# H-00488_-_Connectors_Upstream.net
KiCad netlist of a schematic drawn in Altium Designer
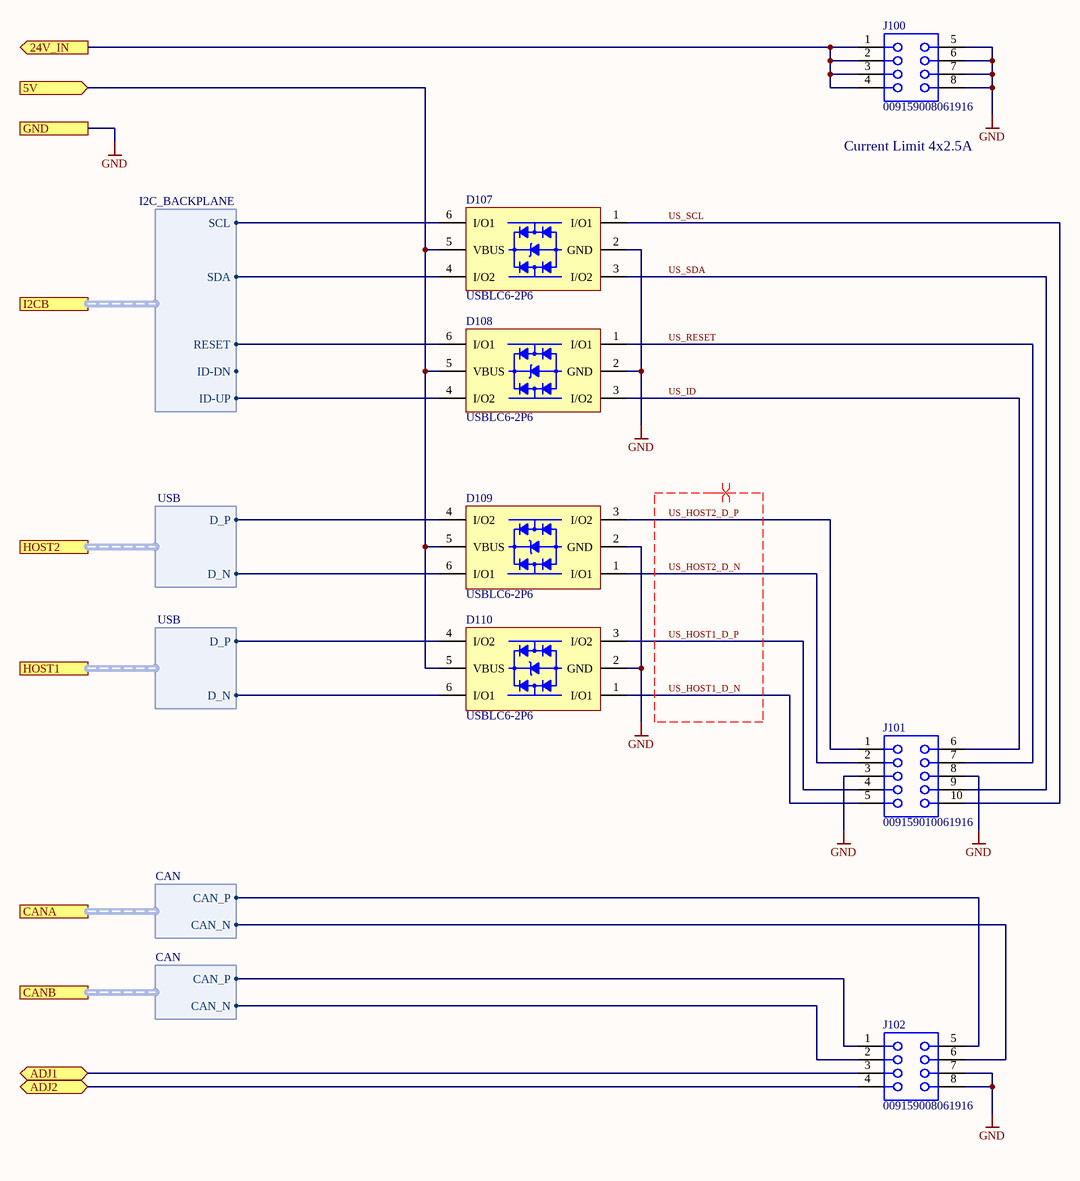
[diagram p0: H-00488 - Connectors Upstream.SchDoc]

(export (version "E")
  (design (tool "Eeschema 10.0.6"))
  (components
    (comp (ref "D107")
      (value "USBLC6-2P6")
      (footprint "DIOSOFL6P50_160X160X95L29X26")
      (description "TVS DIODE 5.25VWM 17VC SOT666")
      (libsource (lib "") (part "ST_USBLC6-2_1"))
    )
    (comp (ref "D108")
      (value "USBLC6-2P6")
      (footprint "DIOSOFL6P50_160X160X95L29X26")
      (description "TVS DIODE 5.25VWM 17VC SOT666")
      (libsource (lib "") (part "ST_USBLC6-2_1"))
    )
    (comp (ref "D109")
      (value "USBLC6-2P6")
      (footprint "DIOSOFL6P50_160X160X95L29X26")
      (description "TVS DIODE 5.25VWM 17VC SOT666")
      (libsource (lib "Hiber") (part "ST_USBLC6-2"))
    )
    (comp (ref "D110")
      (value "USBLC6-2P6")
      (footprint "DIOSOFL6P50_160X160X95L29X26")
      (description "TVS DIODE 5.25VWM 17VC SOT666")
      (libsource (lib "Hiber") (part "ST_USBLC6-2"))
    )
    (comp (ref "J100")
      (value "009159008061916")
      (footprint "AVX_00-9159-008")
      (description "CONN SSL BRIDGE 8POS 2MM")
      (libsource (lib "Hiber") (part "HEADER-FEMALE-02X04-N"))
    )
    (comp (ref "J101")
      (value "009159010061916")
      (footprint "AVX_00-9159-010")
      (description "AVX INTERCONNECT - 009159010061916 - CARD EDGE CONN, DUAL SIDE, 10POS, SMD")
      (libsource (lib "Hiber") (part "HEADER-FEMALE-02X05-N"))
    )
    (comp (ref "J102")
      (value "009159008061916")
      (footprint "AVX_00-9159-008")
      (description "CONN SSL BRIDGE 8POS 2MM")
      (libsource (lib "Hiber") (part "HEADER-FEMALE-02X04-N"))
    )
  )
  (nets
    (net (code "4") (name "/5V") (class "Default")
      (node (ref "D107") (pin "5") (pinfunction "VBUS_5") (pintype "passive"))
      (node (ref "D108") (pin "5") (pinfunction "VBUS_5") (pintype "passive"))
      (node (ref "D109") (pin "5") (pinfunction "VBUS_5") (pintype "passive"))
      (node (ref "D110") (pin "5") (pinfunction "VBUS_5") (pintype "passive"))
    )
    (net (code "5") (name "/24V_IN") (class "Default")
      (node (ref "J100") (pin "1") (pinfunction "1_1") (pintype "passive"))
      (node (ref "J100") (pin "2") (pinfunction "2_2") (pintype "passive"))
      (node (ref "J100") (pin "3") (pinfunction "3_3") (pintype "passive"))
      (node (ref "J100") (pin "4") (pinfunction "4_4") (pintype "passive"))
    )
    (net (code "6") (name "/ADJ1") (class "Default")
      (node (ref "J102") (pin "3") (pinfunction "3_3") (pintype "passive"))
    )
    (net (code "7") (name "/ADJ2") (class "Default")
      (node (ref "J102") (pin "4") (pinfunction "4_4") (pintype "passive"))
    )
    (net (code "8") (name "/ID-UP") (class "Default")
      (node (ref "D108") (pin "4") (pinfunction "I/O2_4") (pintype "passive"))
    )
    (net (code "9") (name "/RESET") (class "Default")
      (node (ref "D108") (pin "6") (pinfunction "I/O1_6") (pintype "passive"))
    )
    (net (code "10") (name "/SCL") (class "Default")
      (node (ref "D107") (pin "6") (pinfunction "I/O1_6") (pintype "passive"))
    )
    (net (code "11") (name "/SDA") (class "Default")
      (node (ref "D107") (pin "4") (pinfunction "I/O2_4") (pintype "passive"))
    )
    (net (code "12") (name "/US_HOST1_D_N") (class "Default")
      (node (ref "D110") (pin "1") (pinfunction "I/O1_1") (pintype "passive"))
      (node (ref "J101") (pin "5") (pinfunction "5_5") (pintype "passive"))
    )
    (net (code "13") (name "/US_HOST1_D_P") (class "Default")
      (node (ref "D110") (pin "3") (pinfunction "I/O2_3") (pintype "passive"))
      (node (ref "J101") (pin "4") (pinfunction "4_4") (pintype "passive"))
    )
    (net (code "14") (name "/US_HOST2_D_N") (class "Default")
      (node (ref "D109") (pin "1") (pinfunction "I/O1_1") (pintype "passive"))
      (node (ref "J101") (pin "2") (pinfunction "2_2") (pintype "passive"))
    )
    (net (code "15") (name "/US_HOST2_D_P") (class "Default")
      (node (ref "D109") (pin "3") (pinfunction "I/O2_3") (pintype "passive"))
      (node (ref "J101") (pin "1") (pinfunction "1_1") (pintype "passive"))
    )
    (net (code "16") (name "/US_ID") (class "Default")
      (node (ref "D108") (pin "3") (pinfunction "I/O2_3") (pintype "passive"))
      (node (ref "J101") (pin "6") (pinfunction "6_6") (pintype "passive"))
    )
    (net (code "17") (name "/US_RESET") (class "Default")
      (node (ref "D108") (pin "1") (pinfunction "I/O1_1") (pintype "passive"))
      (node (ref "J101") (pin "7") (pinfunction "7_7") (pintype "passive"))
    )
    (net (code "18") (name "/US_SCL") (class "Default")
      (node (ref "D107") (pin "1") (pinfunction "I/O1_1") (pintype "passive"))
      (node (ref "J101") (pin "10") (pinfunction "10_10") (pintype "passive"))
    )
    (net (code "19") (name "/US_SDA") (class "Default")
      (node (ref "D107") (pin "3") (pinfunction "I/O2_3") (pintype "passive"))
      (node (ref "J101") (pin "9") (pinfunction "9_9") (pintype "passive"))
    )
    (net (code "23") (name "GND") (class "Default")
      (node (ref "D107") (pin "2") (pinfunction "GND_2") (pintype "passive"))
      (node (ref "D108") (pin "2") (pinfunction "GND_2") (pintype "passive"))
      (node (ref "D109") (pin "2") (pinfunction "GND_2") (pintype "passive"))
      (node (ref "D110") (pin "2") (pinfunction "GND_2") (pintype "passive"))
      (node (ref "J100") (pin "5") (pinfunction "5_5") (pintype "passive"))
      (node (ref "J100") (pin "6") (pinfunction "6_6") (pintype "passive"))
      (node (ref "J100") (pin "7") (pinfunction "7_7") (pintype "passive"))
      (node (ref "J100") (pin "8") (pinfunction "8_8") (pintype "passive"))
      (node (ref "J101") (pin "3") (pinfunction "3_3") (pintype "passive"))
      (node (ref "J101") (pin "8") (pinfunction "8_8") (pintype "passive"))
      (node (ref "J102") (pin "7") (pinfunction "7_7") (pintype "passive"))
      (node (ref "J102") (pin "8") (pinfunction "8_8") (pintype "passive"))
    )
    (net (code "24") (name "unconnected-(D109-I{slash}O1-Pad6)") (class "Default")
      (node (ref "D109") (pin "6") (pinfunction "I/O1_6") (pintype "passive"))
    )
    (net (code "25") (name "unconnected-(D109-I{slash}O2-Pad4)") (class "Default")
      (node (ref "D109") (pin "4") (pinfunction "I/O2_4") (pintype "passive"))
    )
    (net (code "26") (name "unconnected-(D110-I{slash}O1-Pad6)") (class "Default")
      (node (ref "D110") (pin "6") (pinfunction "I/O1_6") (pintype "passive"))
    )
    (net (code "27") (name "unconnected-(D110-I{slash}O2-Pad4)") (class "Default")
      (node (ref "D110") (pin "4") (pinfunction "I/O2_4") (pintype "passive"))
    )
    (net (code "28") (name "unconnected-(J102-Pad1)") (class "Default")
      (node (ref "J102") (pin "1") (pinfunction "1_1") (pintype "passive"))
    )
    (net (code "29") (name "unconnected-(J102-Pad2)") (class "Default")
      (node (ref "J102") (pin "2") (pinfunction "2_2") (pintype "passive"))
    )
    (net (code "30") (name "unconnected-(J102-Pad5)") (class "Default")
      (node (ref "J102") (pin "5") (pinfunction "5_5") (pintype "passive"))
    )
    (net (code "31") (name "unconnected-(J102-Pad6)") (class "Default")
      (node (ref "J102") (pin "6") (pinfunction "6_6") (pintype "passive"))
    )
  )
)
